# Sheet2.net
KiCad netlist of a schematic drawn in Altium Designer
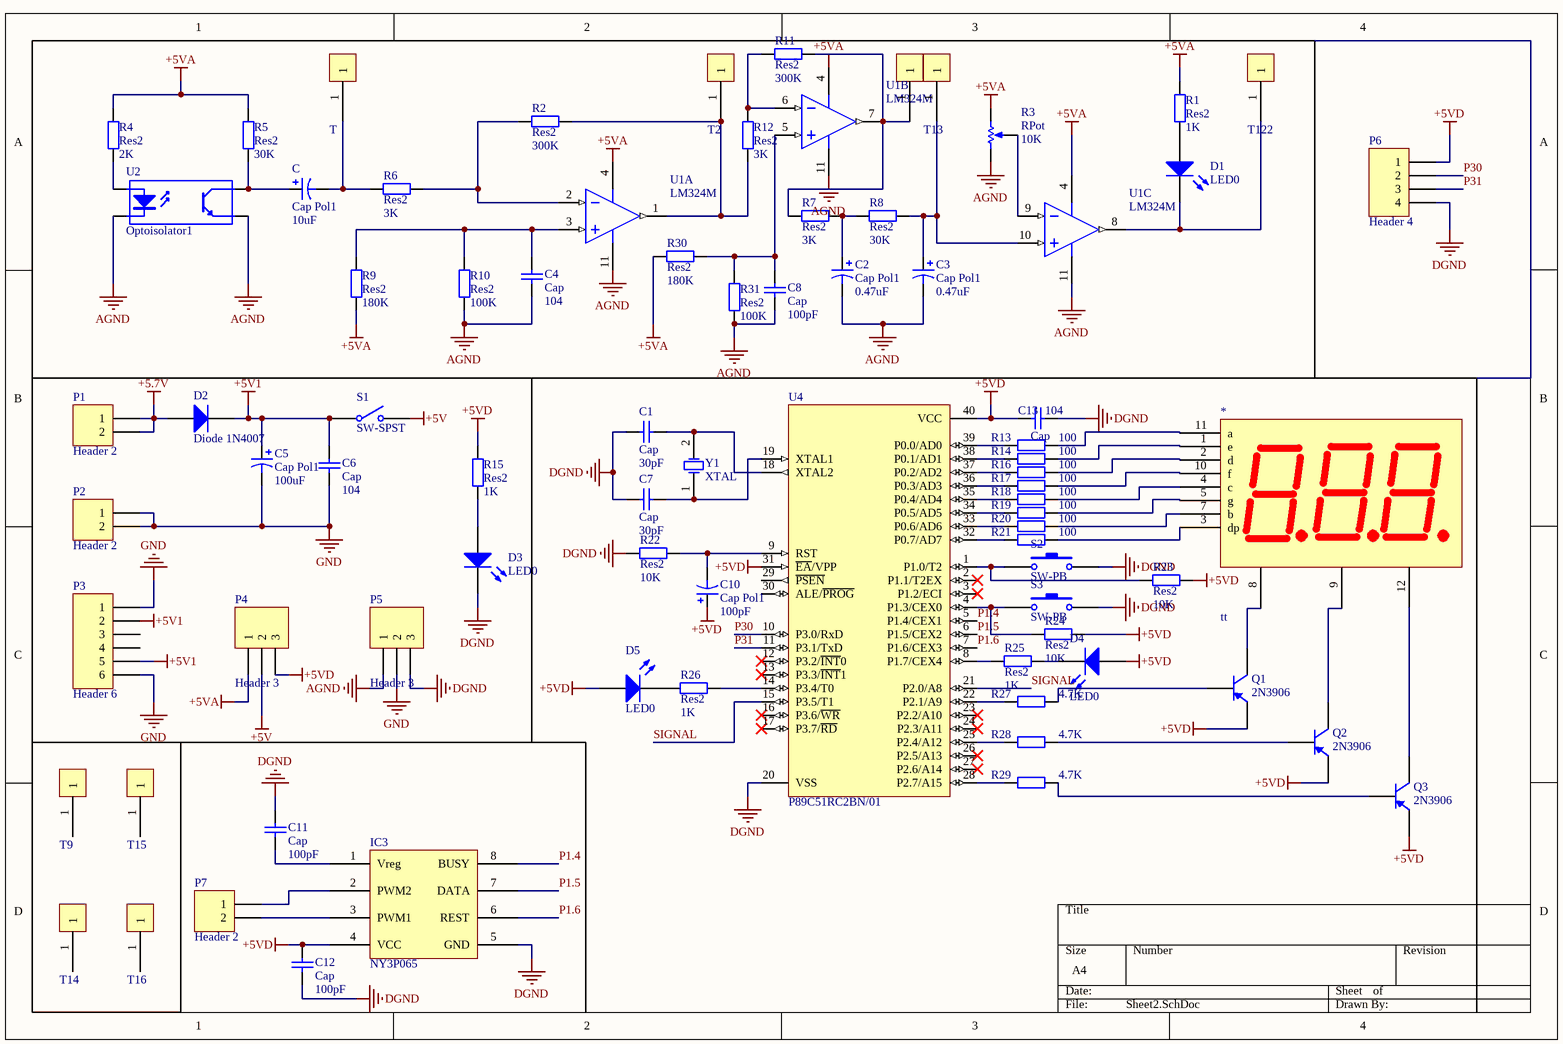
[diagram p0: Sheet2.SchDoc]

(export (version "E")
  (design (tool "Eeschema 10.0.6"))
  (components
    (comp (ref "*") (value "tt") (footprint "smg") (libsource (lib "Schlib1") (part "tt")))
    (comp (ref "C")
      (value "Cap Pol1")
      (footprint "cd-0.1t")
      (description "Polarized Capacitor (Radial)")
      (fields (field (name "ALTIUM_VALUE") "10uF") (field (name "PUBLISHER") "Altium Limited"))
      (libsource (lib "Miscellaneous Devices") (part "Cap Pol1"))
    )
    (comp (ref "C1")
      (value "Cap")
      (footprint "C-0.1")
      (description "Capacitor")
      (fields (field (name "ALTIUM_VALUE") "30pF") (field (name "PUBLISHER") "Altium Limited"))
      (libsource (lib "Miscellaneous Devices") (part "Cap"))
    )
    (comp (ref "C2")
      (value "Cap Pol1")
      (footprint "cd-0.1t")
      (description "Polarized Capacitor (Radial)")
      (fields (field (name "ALTIUM_VALUE") "0.47uF") (field (name "PUBLISHER") "Altium Limited"))
      (libsource (lib "Miscellaneous Devices") (part "Cap Pol1"))
    )
    (comp (ref "C3")
      (value "Cap Pol1")
      (footprint "cd-0.1t")
      (description "Polarized Capacitor (Radial)")
      (fields (field (name "ALTIUM_VALUE") "0.47uF") (field (name "PUBLISHER") "Altium Limited"))
      (libsource (lib "Miscellaneous Devices") (part "Cap Pol1"))
    )
    (comp (ref "C4")
      (value "Cap")
      (footprint "C-0.1")
      (description "Capacitor")
      (fields (field (name "ALTIUM_VALUE") "104") (field (name "PUBLISHER") "Altium Limited"))
      (libsource (lib "Miscellaneous Devices") (part "Cap"))
    )
    (comp (ref "C5")
      (value "Cap Pol1")
      (footprint "CD-0.2T")
      (description "Polarized Capacitor (Radial)")
      (fields (field (name "ALTIUM_VALUE") "100uF") (field (name "PUBLISHER") "Altium Limited"))
      (libsource (lib "Miscellaneous Devices") (part "Cap Pol1"))
    )
    (comp (ref "C6")
      (value "Cap")
      (footprint "C-0.1")
      (description "Capacitor")
      (fields (field (name "ALTIUM_VALUE") "104") (field (name "PUBLISHER") "Altium Limited"))
      (libsource (lib "Miscellaneous Devices") (part "Cap"))
    )
    (comp (ref "C7")
      (value "Cap")
      (footprint "C-0.1")
      (description "Capacitor")
      (fields (field (name "ALTIUM_VALUE") "30pF") (field (name "PUBLISHER") "Altium Limited"))
      (libsource (lib "Miscellaneous Devices") (part "Cap"))
    )
    (comp (ref "C8")
      (value "Cap")
      (footprint "C-0.1")
      (description "Capacitor")
      (fields (field (name "ALTIUM_VALUE") "100pF") (field (name "PUBLISHER") "Altium Limited"))
      (libsource (lib "Miscellaneous Devices") (part "Cap"))
    )
    (comp (ref "C10")
      (value "Cap Pol1")
      (footprint "cd-0.1t")
      (description "Polarized Capacitor (Radial)")
      (fields (field (name "ALTIUM_VALUE") "100pF") (field (name "PUBLISHER") "Altium Limited"))
      (libsource (lib "Miscellaneous Devices") (part "Cap Pol1"))
    )
    (comp (ref "C11")
      (value "Cap")
      (footprint "C0805R")
      (description "Capacitor")
      (fields (field (name "ALTIUM_VALUE") "100pF") (field (name "PUBLISHER") "Altium Limited"))
      (libsource (lib "Miscellaneous Devices") (part "Cap"))
    )
    (comp (ref "C12")
      (value "Cap")
      (footprint "C0805R")
      (description "Capacitor")
      (fields (field (name "ALTIUM_VALUE") "100pF") (field (name "PUBLISHER") "Altium Limited"))
      (libsource (lib "Miscellaneous Devices") (part "Cap"))
    )
    (comp (ref "C13")
      (value "Cap")
      (footprint "C-0.1")
      (description "Capacitor")
      (fields (field (name "ALTIUM_VALUE") "104") (field (name "PUBLISHER") "Altium Limited"))
      (libsource (lib "Miscellaneous Devices") (part "Cap"))
    )
    (comp (ref "D1")
      (value "LED0")
      (footprint "led5")
      (description "Typical INFRARED GaAs LED")
      (fields (field (name "PUBLISHER") "Altium Limited"))
      (libsource (lib "Miscellaneous Devices") (part "LED0"))
    )
    (comp (ref "D2")
      (value "Diode 1N4007")
      (footprint "DO-41")
      (description "1 Amp General Purpose Rectifier")
      (fields (field (name "PUBLISHER") "Altium Limited"))
      (libsource (lib "Miscellaneous Devices") (part "Diode 1N4007"))
    )
    (comp (ref "D3")
      (value "LED0")
      (footprint "led5")
      (description "Typical INFRARED GaAs LED")
      (fields (field (name "PUBLISHER") "Altium Limited"))
      (libsource (lib "Miscellaneous Devices") (part "LED0"))
    )
    (comp (ref "D4")
      (value "LED0")
      (footprint "led5")
      (description "Typical INFRARED GaAs LED")
      (fields (field (name "PUBLISHER") "Altium Limited"))
      (libsource (lib "Miscellaneous Devices") (part "LED0"))
    )
    (comp (ref "D5")
      (value "LED0")
      (footprint "led5")
      (description "Typical INFRARED GaAs LED")
      (fields (field (name "PUBLISHER") "Altium Limited"))
      (libsource (lib "Miscellaneous Devices") (part "LED0"))
    )
    (comp (ref "IC3") (value "NY3P065") (footprint "sop8") (libsource (lib "EPL Scblib") (part "SOUND")))
    (comp (ref "P1")
      (value "Header 2")
      (footprint "SIP2")
      (description "Header, 2-Pin")
      (fields (field (name "PUBLISHER") "Altium Limited"))
      (libsource (lib "Miscellaneous Connectors") (part "Header 2"))
    )
    (comp (ref "P2")
      (value "Header 2")
      (footprint "SIP2")
      (description "Header, 2-Pin")
      (fields (field (name "PUBLISHER") "Altium Limited"))
      (libsource (lib "Miscellaneous Connectors") (part "Header 2"))
    )
    (comp (ref "P3")
      (value "Header 6")
      (footprint "USBTYPEC6")
      (description "Header, 6-Pin")
      (fields (field (name "PUBLISHER") "Altium Limited"))
      (libsource (lib "Miscellaneous Connectors") (part "Header 6"))
    )
    (comp (ref "P4")
      (value "Header 3")
      (footprint "JUMP3")
      (description "Header, 3-Pin")
      (fields (field (name "PUBLISHER") "Altium Limited"))
      (libsource (lib "Miscellaneous Connectors") (part "Header 3"))
    )
    (comp (ref "P5")
      (value "Header 3")
      (footprint "JUMP3")
      (description "Header, 3-Pin")
      (fields (field (name "PUBLISHER") "Altium Limited"))
      (libsource (lib "Miscellaneous Connectors") (part "Header 3"))
    )
    (comp (ref "P6")
      (value "Header 4")
      (footprint "SIP4")
      (description "Header, 4-Pin")
      (fields (field (name "PUBLISHER") "Altium Limited"))
      (libsource (lib "Miscellaneous Connectors") (part "Header 4"))
    )
    (comp (ref "P7")
      (value "Header 2")
      (footprint "BEEP2")
      (description "Header, 2-Pin")
      (fields (field (name "PUBLISHER") "Altium Limited"))
      (libsource (lib "Miscellaneous Connectors") (part "Header 2"))
    )
    (comp (ref "Q1")
      (value "2N3906")
      (footprint "TO92C")
      (description "PNP General Purpose Amplifier")
      (fields (field (name "PUBLISHER") "Altium Limited"))
      (libsource (lib "Miscellaneous Devices") (part "2N3906"))
    )
    (comp (ref "Q2")
      (value "2N3906")
      (footprint "TO92C")
      (description "PNP General Purpose Amplifier")
      (fields (field (name "PUBLISHER") "Altium Limited"))
      (libsource (lib "Miscellaneous Devices") (part "2N3906"))
    )
    (comp (ref "Q3")
      (value "2N3906")
      (footprint "TO92C")
      (description "PNP General Purpose Amplifier")
      (fields (field (name "PUBLISHER") "Altium Limited"))
      (libsource (lib "Miscellaneous Devices") (part "2N3906"))
    )
    (comp (ref "R1")
      (value "Res2")
      (footprint "R-0.3")
      (description "Resistor")
      (fields (field (name "ALTIUM_VALUE") "1K") (field (name "PUBLISHER") "Altium Limited"))
      (libsource (lib "") (part "Res2_2"))
    )
    (comp (ref "R2")
      (value "Res2")
      (footprint "R-0.3")
      (description "Resistor")
      (fields (field (name "ALTIUM_VALUE") "300K") (field (name "PUBLISHER") "Altium Limited"))
      (libsource (lib "Miscellaneous Devices") (part "Res2"))
    )
    (comp (ref "R3")
      (value "RPot")
      (footprint "3362P")
      (description "Potentiometer")
      (fields (field (name "ALTIUM_VALUE") "10K") (field (name "PUBLISHER") "Altium Limited"))
      (libsource (lib "Miscellaneous Devices") (part "RPot"))
    )
    (comp (ref "R4")
      (value "Res2")
      (footprint "R-0.3")
      (description "Resistor")
      (fields (field (name "ALTIUM_VALUE") "2K") (field (name "PUBLISHER") "Altium Limited"))
      (libsource (lib "") (part "Res2_2"))
    )
    (comp (ref "R5")
      (value "Res2")
      (footprint "R-0.3")
      (description "Resistor")
      (fields (field (name "ALTIUM_VALUE") "30K") (field (name "PUBLISHER") "Altium Limited"))
      (libsource (lib "") (part "Res2_2"))
    )
    (comp (ref "R6")
      (value "Res2")
      (footprint "R-0.3")
      (description "Resistor")
      (fields (field (name "ALTIUM_VALUE") "3K") (field (name "PUBLISHER") "Altium Limited"))
      (libsource (lib "Miscellaneous Devices") (part "Res2"))
    )
    (comp (ref "R7")
      (value "Res2")
      (footprint "R-0.3")
      (description "Resistor")
      (fields (field (name "ALTIUM_VALUE") "3K") (field (name "PUBLISHER") "Altium Limited"))
      (libsource (lib "Miscellaneous Devices") (part "Res2"))
    )
    (comp (ref "R8")
      (value "Res2")
      (footprint "R-0.3")
      (description "Resistor")
      (fields (field (name "ALTIUM_VALUE") "30K") (field (name "PUBLISHER") "Altium Limited"))
      (libsource (lib "Miscellaneous Devices") (part "Res2"))
    )
    (comp (ref "R9")
      (value "Res2")
      (footprint "R-0.3")
      (description "Resistor")
      (fields (field (name "ALTIUM_VALUE") "180K") (field (name "PUBLISHER") "Altium Limited"))
      (libsource (lib "") (part "Res2_1"))
    )
    (comp (ref "R10")
      (value "Res2")
      (footprint "R-0.3")
      (description "Resistor")
      (fields (field (name "ALTIUM_VALUE") "100K") (field (name "PUBLISHER") "Altium Limited"))
      (libsource (lib "") (part "Res2_1"))
    )
    (comp (ref "R11")
      (value "Res2")
      (footprint "R-0.3")
      (description "Resistor")
      (fields (field (name "ALTIUM_VALUE") "300K") (field (name "PUBLISHER") "Altium Limited"))
      (libsource (lib "Miscellaneous Devices") (part "Res2"))
    )
    (comp (ref "R12")
      (value "Res2")
      (footprint "R-0.3")
      (description "Resistor")
      (fields (field (name "ALTIUM_VALUE") "3K") (field (name "PUBLISHER") "Altium Limited"))
      (libsource (lib "") (part "Res2_2"))
    )
    (comp (ref "R13")
      (value "100")
      (footprint "R-0.3")
      (description "Resistor")
      (fields (field (name "PUBLISHER") "Altium Limited"))
      (libsource (lib "Miscellaneous Devices") (part "Res2"))
    )
    (comp (ref "R14")
      (value "100")
      (footprint "R-0.3")
      (description "Resistor")
      (fields (field (name "PUBLISHER") "Altium Limited"))
      (libsource (lib "Miscellaneous Devices") (part "Res2"))
    )
    (comp (ref "R15")
      (value "Res2")
      (footprint "R-0.3")
      (description "Resistor")
      (fields (field (name "ALTIUM_VALUE") "1K") (field (name "PUBLISHER") "Altium Limited"))
      (libsource (lib "") (part "Res2_1"))
    )
    (comp (ref "R16")
      (value "100")
      (footprint "R-0.3")
      (description "Resistor")
      (fields (field (name "PUBLISHER") "Altium Limited"))
      (libsource (lib "Miscellaneous Devices") (part "Res2"))
    )
    (comp (ref "R17")
      (value "100")
      (footprint "R-0.3")
      (description "Resistor")
      (fields (field (name "PUBLISHER") "Altium Limited"))
      (libsource (lib "Miscellaneous Devices") (part "Res2"))
    )
    (comp (ref "R18")
      (value "100")
      (footprint "R-0.3")
      (description "Resistor")
      (fields (field (name "PUBLISHER") "Altium Limited"))
      (libsource (lib "Miscellaneous Devices") (part "Res2"))
    )
    (comp (ref "R19")
      (value "100")
      (footprint "R-0.3")
      (description "Resistor")
      (fields (field (name "PUBLISHER") "Altium Limited"))
      (libsource (lib "Miscellaneous Devices") (part "Res2"))
    )
    (comp (ref "R20")
      (value "100")
      (footprint "R-0.3")
      (description "Resistor")
      (fields (field (name "PUBLISHER") "Altium Limited"))
      (libsource (lib "Miscellaneous Devices") (part "Res2"))
    )
    (comp (ref "R21")
      (value "100")
      (footprint "R-0.3")
      (description "Resistor")
      (fields (field (name "PUBLISHER") "Altium Limited"))
      (libsource (lib "Miscellaneous Devices") (part "Res2"))
    )
    (comp (ref "R22")
      (value "Res2")
      (footprint "R-0.3")
      (description "Resistor")
      (fields (field (name "ALTIUM_VALUE") "10K") (field (name "PUBLISHER") "Altium Limited"))
      (libsource (lib "Miscellaneous Devices") (part "Res2"))
    )
    (comp (ref "R23")
      (value "Res2")
      (footprint "R-0.3")
      (description "Resistor")
      (fields (field (name "ALTIUM_VALUE") "10K") (field (name "PUBLISHER") "Altium Limited"))
      (libsource (lib "Miscellaneous Devices") (part "Res2"))
    )
    (comp (ref "R24")
      (value "Res2")
      (footprint "R-0.3")
      (description "Resistor")
      (fields (field (name "ALTIUM_VALUE") "10K") (field (name "PUBLISHER") "Altium Limited"))
      (libsource (lib "Miscellaneous Devices") (part "Res2"))
    )
    (comp (ref "R25")
      (value "Res2")
      (footprint "R-0.3")
      (description "Resistor")
      (fields (field (name "ALTIUM_VALUE") "1K") (field (name "PUBLISHER") "Altium Limited"))
      (libsource (lib "Miscellaneous Devices") (part "Res2"))
    )
    (comp (ref "R26")
      (value "Res2")
      (footprint "R-0.3")
      (description "Resistor")
      (fields (field (name "ALTIUM_VALUE") "1K") (field (name "PUBLISHER") "Altium Limited"))
      (libsource (lib "Miscellaneous Devices") (part "Res2"))
    )
    (comp (ref "R27")
      (value "4.7K")
      (footprint "R-0.3")
      (description "Resistor")
      (fields (field (name "PUBLISHER") "Altium Limited"))
      (libsource (lib "Miscellaneous Devices") (part "Res2"))
    )
    (comp (ref "R28")
      (value "4.7K")
      (footprint "R-0.3")
      (description "Resistor")
      (fields (field (name "PUBLISHER") "Altium Limited"))
      (libsource (lib "Miscellaneous Devices") (part "Res2"))
    )
    (comp (ref "R29")
      (value "4.7K")
      (footprint "R-0.3")
      (description "Resistor")
      (fields (field (name "PUBLISHER") "Altium Limited"))
      (libsource (lib "Miscellaneous Devices") (part "Res2"))
    )
    (comp (ref "R30")
      (value "Res2")
      (footprint "R-0.3")
      (description "Resistor")
      (fields (field (name "ALTIUM_VALUE") "180K") (field (name "PUBLISHER") "Altium Limited"))
      (libsource (lib "") (part "Res2_3"))
    )
    (comp (ref "R31")
      (value "Res2")
      (footprint "R-0.3")
      (description "Resistor")
      (fields (field (name "ALTIUM_VALUE") "100K") (field (name "PUBLISHER") "Altium Limited"))
      (libsource (lib "") (part "Res2_2"))
    )
    (comp (ref "S1")
      (value "SW-SPST")
      (footprint "POW3")
      (description "Single-Pole, Single-Throw Switch")
      (fields (field (name "PUBLISHER") "Altium Limited"))
      (libsource (lib "Miscellaneous Devices") (part "SW-SPST"))
    )
    (comp (ref "S2")
      (value "SW-PB")
      (footprint "key")
      (description "Switch")
      (fields (field (name "PUBLISHER") "Altium Limited"))
      (libsource (lib "Miscellaneous Devices") (part "SW-PB"))
    )
    (comp (ref "S3")
      (value "SW-PB")
      (footprint "key")
      (description "Switch")
      (fields (field (name "PUBLISHER") "Altium Limited"))
      (libsource (lib "Miscellaneous Devices") (part "SW-PB"))
    )
    (comp (ref "T") (value "TEST") (footprint "SIP1") (libsource (lib "EPL Scblib") (part "TEST")))
    (comp (ref "T2") (value "TEST") (footprint "SIP1") (libsource (lib "EPL Scblib") (part "TEST")))
    (comp (ref "T9") (value "TEST") (footprint "HLS") (libsource (lib "EPL Scblib") (part "TEST")))
    (comp (ref "T13") (value "TEST") (footprint "SIP1") (libsource (lib "EPL Scblib") (part "TEST")))
    (comp (ref "T14") (value "TEST") (footprint "HLS") (libsource (lib "EPL Scblib") (part "TEST")))
    (comp (ref "T15") (value "TEST") (footprint "HLS") (libsource (lib "EPL Scblib") (part "TEST")))
    (comp (ref "T16") (value "TEST") (footprint "HLS") (libsource (lib "EPL Scblib") (part "TEST")))
    (comp (ref "T122") (value "TEST") (footprint "SIP1") (libsource (lib "EPL Scblib") (part "TEST")))
    (comp (ref "T21122") (value "TEST") (footprint "SIP1") (libsource (lib "EPL Scblib") (part "TEST")))
    (comp (ref "U1")
      (value "LM324M")
      (footprint "DIP14MY")
      (description "Low Power Quad Operational Amplifier")
      (fields
        (field (name "MANUFACTURER") "National Semiconductor")
        (field (name "DIGIKEYPARTNUMBER") "LM324MXCT-ND")
        (field (name "PUBLISHER") "Altium Limited")
      )
      (libsource (lib "NSC Amplifier") (part "LM324M"))
    )
    (comp (ref "U2")
      (value "Optoisolator1")
      (footprint "sen")
      (description "4-Pin Phototransistor Optocoupler")
      (fields (field (name "PUBLISHER") "Altium Limited"))
      (libsource (lib "Miscellaneous Devices") (part "Optoisolator1"))
    )
    (comp (ref "U4")
      (value "P89C51RC2BN/01")
      (footprint "DIP40")
      (description "80C51 8-Bit Flash Microcontroller Family, 32 kB ISP/IAP Flash with 512 B RAM.")
      (fields (field (name "PUBLISHER") "Altium Limited"))
      (libsource (lib "Philips Microcontroller 8-Bit") (part "P89C51RC2BN/01"))
    )
    (comp (ref "Y1")
      (value "XTAL")
      (footprint "jz")
      (description "Crystal Oscillator")
      (fields (field (name "PUBLISHER") "Altium Limited"))
      (libsource (lib "Miscellaneous Devices") (part "XTAL"))
    )
  )
  (nets
    (net (code "1") (name "+5.7V") (class "Default")
      (node (ref "D2") (pin "1") (pinfunction "A_1") (pintype "passive"))
      (node (ref "P1") (pin "1") (pinfunction "1_1") (pintype "passive"))
      (node (ref "P1") (pin "2") (pinfunction "2_2") (pintype "passive"))
    )
    (net (code "2") (name "+5V") (class "Default")
      (node (ref "P4") (pin "2") (pinfunction "2_2") (pintype "passive"))
      (node (ref "S1") (pin "2") (pinfunction "NO_2") (pintype "passive"))
    )
    (net (code "3") (name "+5V1") (class "Default")
      (node (ref "C5") (pin "1") (pinfunction "1_1") (pintype "passive"))
      (node (ref "C6") (pin "1") (pinfunction "1_1") (pintype "passive"))
      (node (ref "D2") (pin "2") (pinfunction "K_2") (pintype "passive"))
      (node (ref "P3") (pin "2") (pinfunction "2_2") (pintype "passive"))
      (node (ref "P3") (pin "5") (pinfunction "5_5") (pintype "passive"))
      (node (ref "S1") (pin "1") (pinfunction "COMMON_1") (pintype "passive"))
    )
    (net (code "4") (name "+5VA") (class "Default")
      (node (ref "P4") (pin "1") (pinfunction "1_1") (pintype "passive"))
      (node (ref "R1") (pin "2") (pinfunction "2_2") (pintype "passive"))
      (node (ref "R3") (pin "2") (pinfunction "BOT_2") (pintype "passive"))
      (node (ref "R30") (pin "2") (pinfunction "2_2") (pintype "passive"))
      (node (ref "R4") (pin "2") (pinfunction "2_2") (pintype "passive"))
      (node (ref "R5") (pin "2") (pinfunction "2_2") (pintype "passive"))
      (node (ref "R9") (pin "2") (pinfunction "2_2") (pintype "passive"))
      (node (ref "U1") (pin "4") (pinfunction "V+_4") (pintype "power_in"))
    )
    (net (code "5") (name "+5VD") (class "Default")
      (node (ref "C10") (pin "1") (pinfunction "1_1") (pintype "passive"))
      (node (ref "C12") (pin "2") (pinfunction "2_2") (pintype "passive"))
      (node (ref "C13") (pin "1") (pinfunction "1_1") (pintype "passive"))
      (node (ref "D4") (pin "1") (pinfunction "A_1") (pintype "passive"))
      (node (ref "D5") (pin "1") (pinfunction "A_1") (pintype "passive"))
      (node (ref "IC3") (pin "4") (pinfunction "VCC_4") (pintype "passive"))
      (node (ref "P4") (pin "3") (pinfunction "3_3") (pintype "passive"))
      (node (ref "P6") (pin "1") (pinfunction "1_1") (pintype "passive"))
      (node (ref "Q1") (pin "1") (pinfunction "E_1") (pintype "passive"))
      (node (ref "Q2") (pin "1") (pinfunction "E_1") (pintype "passive"))
      (node (ref "Q3") (pin "1") (pinfunction "E_1") (pintype "passive"))
      (node (ref "R15") (pin "1") (pinfunction "1_1") (pintype "passive"))
      (node (ref "R23") (pin "2") (pinfunction "2_2") (pintype "passive"))
      (node (ref "R24") (pin "2") (pinfunction "2_2") (pintype "passive"))
      (node (ref "U4") (pin "31") (pinfunction "~{EA}/VPP_31") (pintype "input"))
      (node (ref "U4") (pin "40") (pinfunction "VCC_40") (pintype "power_in"))
    )
    (net (code "6") (name "/P1.4") (class "Default")
      (node (ref "IC3") (pin "8") (pinfunction "BUSY_8") (pintype "passive"))
      (node (ref "U4") (pin "5") (pinfunction "P1.4/CEX1_5") (pintype "bidirectional"))
    )
    (net (code "7") (name "/P1.5") (class "Default")
      (node (ref "IC3") (pin "7") (pinfunction "DATA_7") (pintype "passive"))
      (node (ref "U4") (pin "6") (pinfunction "P1.5/CEX2_6") (pintype "bidirectional"))
    )
    (net (code "8") (name "/P1.6") (class "Default")
      (node (ref "IC3") (pin "6") (pinfunction "REST_6") (pintype "passive"))
      (node (ref "U4") (pin "7") (pinfunction "P1.6/CEX3_7") (pintype "bidirectional"))
    )
    (net (code "9") (name "/P30") (class "Default")
      (node (ref "P6") (pin "2") (pinfunction "2_2") (pintype "passive"))
      (node (ref "U4") (pin "10") (pinfunction "P3.0/RxD_10") (pintype "bidirectional"))
    )
    (net (code "10") (name "/P31") (class "Default")
      (node (ref "P6") (pin "3") (pinfunction "3_3") (pintype "passive"))
      (node (ref "U4") (pin "11") (pinfunction "P3.1/TxD_11") (pintype "bidirectional"))
    )
    (net (code "11") (name "/SIGNAL") (class "Default")
      (node (ref "U4") (pin "15") (pinfunction "P3.5/T1_15") (pintype "bidirectional"))
      (node (ref "U4") (pin "21") (pinfunction "P2.0/A8_21") (pintype "bidirectional"))
    )
    (net (code "12") (name "AGND") (class "Default")
      (node (ref "C2") (pin "2") (pinfunction "2_2") (pintype "passive"))
      (node (ref "C3") (pin "2") (pinfunction "2_2") (pintype "passive"))
      (node (ref "C4") (pin "1") (pinfunction "1_1") (pintype "passive"))
      (node (ref "C8") (pin "1") (pinfunction "1_1") (pintype "passive"))
      (node (ref "P5") (pin "1") (pinfunction "1_1") (pintype "passive"))
      (node (ref "R10") (pin "2") (pinfunction "2_2") (pintype "passive"))
      (node (ref "R3") (pin "1") (pinfunction "TOP_1") (pintype "passive"))
      (node (ref "R31") (pin "1") (pinfunction "1_1") (pintype "passive"))
      (node (ref "U1") (pin "11") (pinfunction "GND_11") (pintype "power_in"))
      (node (ref "U2") (pin "2") (pinfunction "K_2") (pintype "passive"))
      (node (ref "U2") (pin "3") (pinfunction "E_3") (pintype "passive"))
    )
    (net (code "13") (name "DGND") (class "Default")
      (node (ref "C1") (pin "1") (pinfunction "1_1") (pintype "passive"))
      (node (ref "C11") (pin "2") (pinfunction "2_2") (pintype "passive"))
      (node (ref "C12") (pin "1") (pinfunction "1_1") (pintype "passive"))
      (node (ref "C13") (pin "2") (pinfunction "2_2") (pintype "passive"))
      (node (ref "C7") (pin "2") (pinfunction "2_2") (pintype "passive"))
      (node (ref "D3") (pin "2") (pinfunction "K_2") (pintype "passive"))
      (node (ref "IC3") (pin "5") (pinfunction "GND_5") (pintype "passive"))
      (node (ref "P5") (pin "3") (pinfunction "3_3") (pintype "passive"))
      (node (ref "P6") (pin "4") (pinfunction "4_4") (pintype "passive"))
      (node (ref "R22") (pin "1") (pinfunction "1_1") (pintype "passive"))
      (node (ref "S2") (pin "2") (pinfunction "2_2") (pintype "passive"))
      (node (ref "S3") (pin "2") (pinfunction "2_2") (pintype "passive"))
      (node (ref "U4") (pin "20") (pinfunction "VSS_20") (pintype "power_in"))
    )
    (net (code "14") (name "GND") (class "Default")
      (node (ref "C5") (pin "2") (pinfunction "2_2") (pintype "passive"))
      (node (ref "C6") (pin "2") (pinfunction "2_2") (pintype "passive"))
      (node (ref "P2") (pin "1") (pinfunction "1_1") (pintype "passive"))
      (node (ref "P2") (pin "2") (pinfunction "2_2") (pintype "passive"))
      (node (ref "P3") (pin "1") (pinfunction "1_1") (pintype "passive"))
      (node (ref "P3") (pin "6") (pinfunction "6_6") (pintype "passive"))
      (node (ref "P5") (pin "2") (pinfunction "2_2") (pintype "passive"))
    )
    (net (code "15") (name "Net-(*-13)") (class "Default")
      (node (ref "*") (pin "9") (pinfunction "13_9") (pintype "passive"))
      (node (ref "Q2") (pin "3") (pinfunction "C_3") (pintype "passive"))
    )
    (net (code "16") (name "Net-(*-14)") (class "Default")
      (node (ref "*") (pin "12") (pinfunction "14_12") (pintype "passive"))
      (node (ref "Q3") (pin "3") (pinfunction "C_3") (pintype "passive"))
    )
    (net (code "17") (name "Net-(*-a)") (class "Default")
      (node (ref "*") (pin "11") (pinfunction "a_11") (pintype "passive"))
      (node (ref "R13") (pin "2") (pinfunction "2_2") (pintype "passive"))
    )
    (net (code "18") (name "Net-(*-b)") (class "Default")
      (node (ref "*") (pin "7") (pinfunction "b_7") (pintype "passive"))
      (node (ref "R20") (pin "2") (pinfunction "2_2") (pintype "passive"))
    )
    (net (code "19") (name "Net-(*-c)") (class "Default")
      (node (ref "*") (pin "4") (pinfunction "c_4") (pintype "passive"))
      (node (ref "R18") (pin "2") (pinfunction "2_2") (pintype "passive"))
    )
    (net (code "20") (name "Net-(*-d)") (class "Default")
      (node (ref "*") (pin "2") (pinfunction "d_2") (pintype "passive"))
      (node (ref "R16") (pin "2") (pinfunction "2_2") (pintype "passive"))
    )
    (net (code "21") (name "Net-(*-dp)") (class "Default")
      (node (ref "*") (pin "3") (pinfunction "dp_3") (pintype "passive"))
      (node (ref "R21") (pin "2") (pinfunction "2_2") (pintype "passive"))
    )
    (net (code "22") (name "Net-(*-e)") (class "Default")
      (node (ref "*") (pin "1") (pinfunction "e_1") (pintype "passive"))
      (node (ref "R14") (pin "2") (pinfunction "2_2") (pintype "passive"))
    )
    (net (code "23") (name "Net-(*-f)") (class "Default")
      (node (ref "*") (pin "10") (pinfunction "f_10") (pintype "passive"))
      (node (ref "R17") (pin "2") (pinfunction "2_2") (pintype "passive"))
    )
    (net (code "24") (name "Net-(*-g)") (class "Default")
      (node (ref "*") (pin "5") (pinfunction "g_5") (pintype "passive"))
      (node (ref "R19") (pin "2") (pinfunction "2_2") (pintype "passive"))
    )
    (net (code "25") (name "Net-(C-Pad2)") (class "Default")
      (node (ref "C") (pin "2") (pinfunction "2_2") (pintype "passive"))
      (node (ref "R6") (pin "1") (pinfunction "1_1") (pintype "passive"))
      (node (ref "T") (pin "1") (pinfunction "1_1") (pintype "passive"))
    )
    (net (code "26") (name "Net-(C2-Pad1)") (class "Default")
      (node (ref "C2") (pin "1") (pinfunction "1_1") (pintype "passive"))
      (node (ref "R7") (pin "2") (pinfunction "2_2") (pintype "passive"))
      (node (ref "R8") (pin "1") (pinfunction "1_1") (pintype "passive"))
    )
    (net (code "27") (name "Net-(D1-A)") (class "Default")
      (node (ref "D1") (pin "1") (pinfunction "A_1") (pintype "passive"))
      (node (ref "R1") (pin "1") (pinfunction "1_1") (pintype "passive"))
    )
    (net (code "28") (name "Net-(D1-K)") (class "Default")
      (node (ref "D1") (pin "2") (pinfunction "K_2") (pintype "passive"))
      (node (ref "T122") (pin "1") (pinfunction "1_1") (pintype "passive"))
      (node (ref "U1") (pin "8") (pinfunction "OUT3_8") (pintype "output"))
    )
    (net (code "29") (name "Net-(D3-A)") (class "Default")
      (node (ref "D3") (pin "1") (pinfunction "A_1") (pintype "passive"))
      (node (ref "R15") (pin "2") (pinfunction "2_2") (pintype "passive"))
    )
    (net (code "30") (name "Net-(D4-K)") (class "Default")
      (node (ref "D4") (pin "2") (pinfunction "K_2") (pintype "passive"))
      (node (ref "R25") (pin "2") (pinfunction "2_2") (pintype "passive"))
    )
    (net (code "31") (name "Net-(D5-K)") (class "Default")
      (node (ref "D5") (pin "2") (pinfunction "K_2") (pintype "passive"))
      (node (ref "R26") (pin "1") (pinfunction "1_1") (pintype "passive"))
    )
    (net (code "32") (name "Net-(IC3-PWM1)") (class "Default")
      (node (ref "IC3") (pin "3") (pinfunction "PWM1_3") (pintype "passive"))
      (node (ref "P7") (pin "2") (pinfunction "2_2") (pintype "passive"))
    )
    (net (code "33") (name "Net-(IC3-PWM2)") (class "Default")
      (node (ref "IC3") (pin "2") (pinfunction "PWM2_2") (pintype "passive"))
      (node (ref "P7") (pin "1") (pinfunction "1_1") (pintype "passive"))
    )
    (net (code "34") (name "Net-(IC3-Vreg)") (class "Default")
      (node (ref "C11") (pin "1") (pinfunction "1_1") (pintype "passive"))
      (node (ref "IC3") (pin "1") (pinfunction "Vreg_1") (pintype "passive"))
    )
    (net (code "35") (name "Net-(Q1-B)") (class "Default")
      (node (ref "Q1") (pin "2") (pinfunction "B_2") (pintype "passive"))
      (node (ref "R27") (pin "2") (pinfunction "2_2") (pintype "passive"))
    )
    (net (code "36") (name "Net-(Q1-C)") (class "Default")
      (node (ref "*") (pin "8") (pinfunction "8_8") (pintype "passive"))
      (node (ref "Q1") (pin "3") (pinfunction "C_3") (pintype "passive"))
    )
    (net (code "37") (name "Net-(Q2-B)") (class "Default")
      (node (ref "Q2") (pin "2") (pinfunction "B_2") (pintype "passive"))
      (node (ref "R28") (pin "2") (pinfunction "2_2") (pintype "passive"))
    )
    (net (code "38") (name "Net-(Q3-B)") (class "Default")
      (node (ref "Q3") (pin "2") (pinfunction "B_2") (pintype "passive"))
      (node (ref "R29") (pin "2") (pinfunction "2_2") (pintype "passive"))
    )
    (net (code "39") (name "Net-(R3-TAP)") (class "Default")
      (node (ref "R3") (pin "3") (pinfunction "TAP_3") (pintype "passive"))
      (node (ref "U1") (pin "9") (pinfunction "IN3-_9") (pintype "input"))
    )
    (net (code "40") (name "Net-(U1A-IN1+)") (class "Default")
      (node (ref "C4") (pin "2") (pinfunction "2_2") (pintype "passive"))
      (node (ref "R10") (pin "1") (pinfunction "1_1") (pintype "passive"))
      (node (ref "R9") (pin "1") (pinfunction "1_1") (pintype "passive"))
      (node (ref "U1") (pin "3") (pinfunction "IN1+_3") (pintype "input"))
    )
    (net (code "41") (name "Net-(U1A-IN1-)") (class "Default")
      (node (ref "R2") (pin "1") (pinfunction "1_1") (pintype "passive"))
      (node (ref "R6") (pin "2") (pinfunction "2_2") (pintype "passive"))
      (node (ref "U1") (pin "2") (pinfunction "IN1-_2") (pintype "input"))
    )
    (net (code "42") (name "Net-(U1A-OUT1)") (class "Default")
      (node (ref "R12") (pin "1") (pinfunction "1_1") (pintype "passive"))
      (node (ref "R2") (pin "2") (pinfunction "2_2") (pintype "passive"))
      (node (ref "T2") (pin "1") (pinfunction "1_1") (pintype "passive"))
      (node (ref "U1") (pin "1") (pinfunction "OUT1_1") (pintype "output"))
    )
    (net (code "43") (name "Net-(U1B-IN2+)") (class "Default")
      (node (ref "C8") (pin "2") (pinfunction "2_2") (pintype "passive"))
      (node (ref "R30") (pin "1") (pinfunction "1_1") (pintype "passive"))
      (node (ref "R31") (pin "2") (pinfunction "2_2") (pintype "passive"))
      (node (ref "U1") (pin "5") (pinfunction "IN2+_5") (pintype "input"))
    )
    (net (code "44") (name "Net-(U1B-IN2-)") (class "Default")
      (node (ref "R11") (pin "1") (pinfunction "1_1") (pintype "passive"))
      (node (ref "R12") (pin "2") (pinfunction "2_2") (pintype "passive"))
      (node (ref "U1") (pin "6") (pinfunction "IN2-_6") (pintype "input"))
    )
    (net (code "45") (name "Net-(U1B-OUT2)") (class "Default")
      (node (ref "R11") (pin "2") (pinfunction "2_2") (pintype "passive"))
      (node (ref "R7") (pin "1") (pinfunction "1_1") (pintype "passive"))
      (node (ref "T21122") (pin "1") (pinfunction "1_1") (pintype "passive"))
      (node (ref "U1") (pin "7") (pinfunction "OUT2_7") (pintype "output"))
    )
    (net (code "46") (name "Net-(U1C-IN3+)") (class "Default")
      (node (ref "C3") (pin "1") (pinfunction "1_1") (pintype "passive"))
      (node (ref "R8") (pin "2") (pinfunction "2_2") (pintype "passive"))
      (node (ref "T13") (pin "1") (pinfunction "1_1") (pintype "passive"))
      (node (ref "U1") (pin "10") (pinfunction "IN3+_10") (pintype "input"))
    )
    (net (code "47") (name "Net-(U2-A)") (class "Default")
      (node (ref "R4") (pin "1") (pinfunction "1_1") (pintype "passive"))
      (node (ref "U2") (pin "1") (pinfunction "A_1") (pintype "passive"))
    )
    (net (code "48") (name "Net-(U2-C)") (class "Default")
      (node (ref "C") (pin "1") (pinfunction "1_1") (pintype "passive"))
      (node (ref "R5") (pin "1") (pinfunction "1_1") (pintype "passive"))
      (node (ref "U2") (pin "4") (pinfunction "C_4") (pintype "passive"))
    )
    (net (code "49") (name "Net-(U4-P0.0{slash}AD0)") (class "Default")
      (node (ref "R13") (pin "1") (pinfunction "1_1") (pintype "passive"))
      (node (ref "U4") (pin "39") (pinfunction "P0.0/AD0_39") (pintype "bidirectional"))
    )
    (net (code "50") (name "Net-(U4-P0.1{slash}AD1)") (class "Default")
      (node (ref "R14") (pin "1") (pinfunction "1_1") (pintype "passive"))
      (node (ref "U4") (pin "38") (pinfunction "P0.1/AD1_38") (pintype "bidirectional"))
    )
    (net (code "51") (name "Net-(U4-P0.2{slash}AD2)") (class "Default")
      (node (ref "R16") (pin "1") (pinfunction "1_1") (pintype "passive"))
      (node (ref "U4") (pin "37") (pinfunction "P0.2/AD2_37") (pintype "bidirectional"))
    )
    (net (code "52") (name "Net-(U4-P0.3{slash}AD3)") (class "Default")
      (node (ref "R17") (pin "1") (pinfunction "1_1") (pintype "passive"))
      (node (ref "U4") (pin "36") (pinfunction "P0.3/AD3_36") (pintype "bidirectional"))
    )
    (net (code "53") (name "Net-(U4-P0.4{slash}AD4)") (class "Default")
      (node (ref "R18") (pin "1") (pinfunction "1_1") (pintype "passive"))
      (node (ref "U4") (pin "35") (pinfunction "P0.4/AD4_35") (pintype "bidirectional"))
    )
    (net (code "54") (name "Net-(U4-P0.5{slash}AD5)") (class "Default")
      (node (ref "R19") (pin "1") (pinfunction "1_1") (pintype "passive"))
      (node (ref "U4") (pin "34") (pinfunction "P0.5/AD5_34") (pintype "bidirectional"))
    )
    (net (code "55") (name "Net-(U4-P0.6{slash}AD6)") (class "Default")
      (node (ref "R20") (pin "1") (pinfunction "1_1") (pintype "passive"))
      (node (ref "U4") (pin "33") (pinfunction "P0.6/AD6_33") (pintype "bidirectional"))
    )
    (net (code "56") (name "Net-(U4-P0.7{slash}AD7)") (class "Default")
      (node (ref "R21") (pin "1") (pinfunction "1_1") (pintype "passive"))
      (node (ref "U4") (pin "32") (pinfunction "P0.7/AD7_32") (pintype "bidirectional"))
    )
    (net (code "57") (name "Net-(U4-P1.0{slash}T2)") (class "Default")
      (node (ref "R23") (pin "1") (pinfunction "1_1") (pintype "passive"))
      (node (ref "S2") (pin "1") (pinfunction "1_1") (pintype "passive"))
      (node (ref "U4") (pin "1") (pinfunction "P1.0/T2_1") (pintype "bidirectional"))
    )
    (net (code "58") (name "Net-(U4-P1.3{slash}CEX0)") (class "Default")
      (node (ref "R24") (pin "1") (pinfunction "1_1") (pintype "passive"))
      (node (ref "S3") (pin "1") (pinfunction "1_1") (pintype "passive"))
      (node (ref "U4") (pin "4") (pinfunction "P1.3/CEX0_4") (pintype "bidirectional"))
    )
    (net (code "59") (name "Net-(U4-P1.7{slash}CEX4)") (class "Default")
      (node (ref "R25") (pin "1") (pinfunction "1_1") (pintype "passive"))
      (node (ref "U4") (pin "8") (pinfunction "P1.7/CEX4_8") (pintype "bidirectional"))
    )
    (net (code "60") (name "Net-(U4-P2.1{slash}A9)") (class "Default")
      (node (ref "R27") (pin "1") (pinfunction "1_1") (pintype "passive"))
      (node (ref "U4") (pin "22") (pinfunction "P2.1/A9_22") (pintype "bidirectional"))
    )
    (net (code "61") (name "Net-(U4-P2.4{slash}A12)") (class "Default")
      (node (ref "R28") (pin "1") (pinfunction "1_1") (pintype "passive"))
      (node (ref "U4") (pin "25") (pinfunction "P2.4/A12_25") (pintype "bidirectional"))
    )
    (net (code "62") (name "Net-(U4-P2.7{slash}A15)") (class "Default")
      (node (ref "R29") (pin "1") (pinfunction "1_1") (pintype "passive"))
      (node (ref "U4") (pin "28") (pinfunction "P2.7/A15_28") (pintype "bidirectional"))
    )
    (net (code "63") (name "Net-(U4-P3.4{slash}T0)") (class "Default")
      (node (ref "R26") (pin "2") (pinfunction "2_2") (pintype "passive"))
      (node (ref "U4") (pin "14") (pinfunction "P3.4/T0_14") (pintype "bidirectional"))
    )
    (net (code "64") (name "Net-(U4-RST)") (class "Default")
      (node (ref "C10") (pin "2") (pinfunction "2_2") (pintype "passive"))
      (node (ref "R22") (pin "2") (pinfunction "2_2") (pintype "passive"))
      (node (ref "U4") (pin "9") (pinfunction "RST_9") (pintype "input"))
    )
    (net (code "65") (name "Net-(U4-XTAL1)") (class "Default")
      (node (ref "C7") (pin "1") (pinfunction "1_1") (pintype "passive"))
      (node (ref "U4") (pin "19") (pinfunction "XTAL1_19") (pintype "input"))
      (node (ref "Y1") (pin "1") (pinfunction "OSC1_1") (pintype "passive"))
    )
    (net (code "66") (name "Net-(U4-XTAL2)") (class "Default")
      (node (ref "C1") (pin "2") (pinfunction "2_2") (pintype "passive"))
      (node (ref "U4") (pin "18") (pinfunction "XTAL2_18") (pintype "output"))
      (node (ref "Y1") (pin "2") (pinfunction "OSC2_2") (pintype "passive"))
    )
    (net (code "67") (name "unconnected-(P3-Pad3)") (class "Default")
      (node (ref "P3") (pin "3") (pinfunction "3_3") (pintype "passive"))
    )
    (net (code "68") (name "unconnected-(P3-Pad4)") (class "Default")
      (node (ref "P3") (pin "4") (pinfunction "4_4") (pintype "passive"))
    )
    (net (code "69") (name "unconnected-(T9-Pad1)") (class "Default")
      (node (ref "T9") (pin "1") (pinfunction "1_1") (pintype "passive"))
    )
    (net (code "70") (name "unconnected-(T14-Pad1)") (class "Default")
      (node (ref "T14") (pin "1") (pinfunction "1_1") (pintype "passive"))
    )
    (net (code "71") (name "unconnected-(T15-Pad1)") (class "Default")
      (node (ref "T15") (pin "1") (pinfunction "1_1") (pintype "passive"))
    )
    (net (code "72") (name "unconnected-(T16-Pad1)") (class "Default")
      (node (ref "T16") (pin "1") (pinfunction "1_1") (pintype "passive"))
    )
    (net (code "73") (name "unconnected-(U4-ALE{slash}~{PROG}-Pad30)") (class "Default")
      (node (ref "U4") (pin "30") (pinfunction "ALE/~{PROG}_30") (pintype "bidirectional"))
    )
    (net (code "74") (name "unconnected-(U4-P1.1{slash}T2EX-Pad2)") (class "Default")
      (node (ref "U4") (pin "2") (pinfunction "P1.1/T2EX_2") (pintype "bidirectional+no_connect"))
    )
    (net (code "75") (name "unconnected-(U4-P1.2{slash}ECI-Pad3)") (class "Default")
      (node (ref "U4") (pin "3") (pinfunction "P1.2/ECI_3") (pintype "bidirectional+no_connect"))
    )
    (net (code "76") (name "unconnected-(U4-P2.2{slash}A10-Pad23)") (class "Default")
      (node (ref "U4") (pin "23") (pinfunction "P2.2/A10_23") (pintype "bidirectional+no_connect"))
    )
    (net (code "77") (name "unconnected-(U4-P2.3{slash}A11-Pad24)") (class "Default")
      (node (ref "U4") (pin "24") (pinfunction "P2.3/A11_24") (pintype "bidirectional+no_connect"))
    )
    (net (code "78") (name "unconnected-(U4-P2.5{slash}A13-Pad26)") (class "Default")
      (node (ref "U4") (pin "26") (pinfunction "P2.5/A13_26") (pintype "bidirectional+no_connect"))
    )
    (net (code "79") (name "unconnected-(U4-P2.6{slash}A14-Pad27)") (class "Default")
      (node (ref "U4") (pin "27") (pinfunction "P2.6/A14_27") (pintype "bidirectional+no_connect"))
    )
    (net (code "80") (name "unconnected-(U4-P3.2{slash}~{INT}0-Pad12)") (class "Default")
      (node (ref "U4") (pin "12") (pinfunction "P3.2/~{INT}0_12") (pintype "bidirectional+no_connect"))
    )
    (net (code "81") (name "unconnected-(U4-P3.3{slash}~{INT}1-Pad13)") (class "Default")
      (node (ref "U4") (pin "13") (pinfunction "P3.3/~{INT}1_13") (pintype "bidirectional+no_connect"))
    )
    (net (code "82") (name "unconnected-(U4-P3.6{slash}~{WR}-Pad16)") (class "Default")
      (node (ref "U4") (pin "16") (pinfunction "P3.6/~{WR}_16") (pintype "bidirectional+no_connect"))
    )
    (net (code "83") (name "unconnected-(U4-P3.7{slash}~{RD}-Pad17)") (class "Default")
      (node (ref "U4") (pin "17") (pinfunction "P3.7/~{RD}_17") (pintype "bidirectional+no_connect"))
    )
    (net (code "84") (name "unconnected-(U4-~{PSEN}-Pad29)") (class "Default")
      (node (ref "U4") (pin "29") (pinfunction "~{PSEN}_29") (pintype "output"))
    )
  )
)
